# Sensor-TSL2591.net
KiCad netlist of a schematic drawn in EAGLE
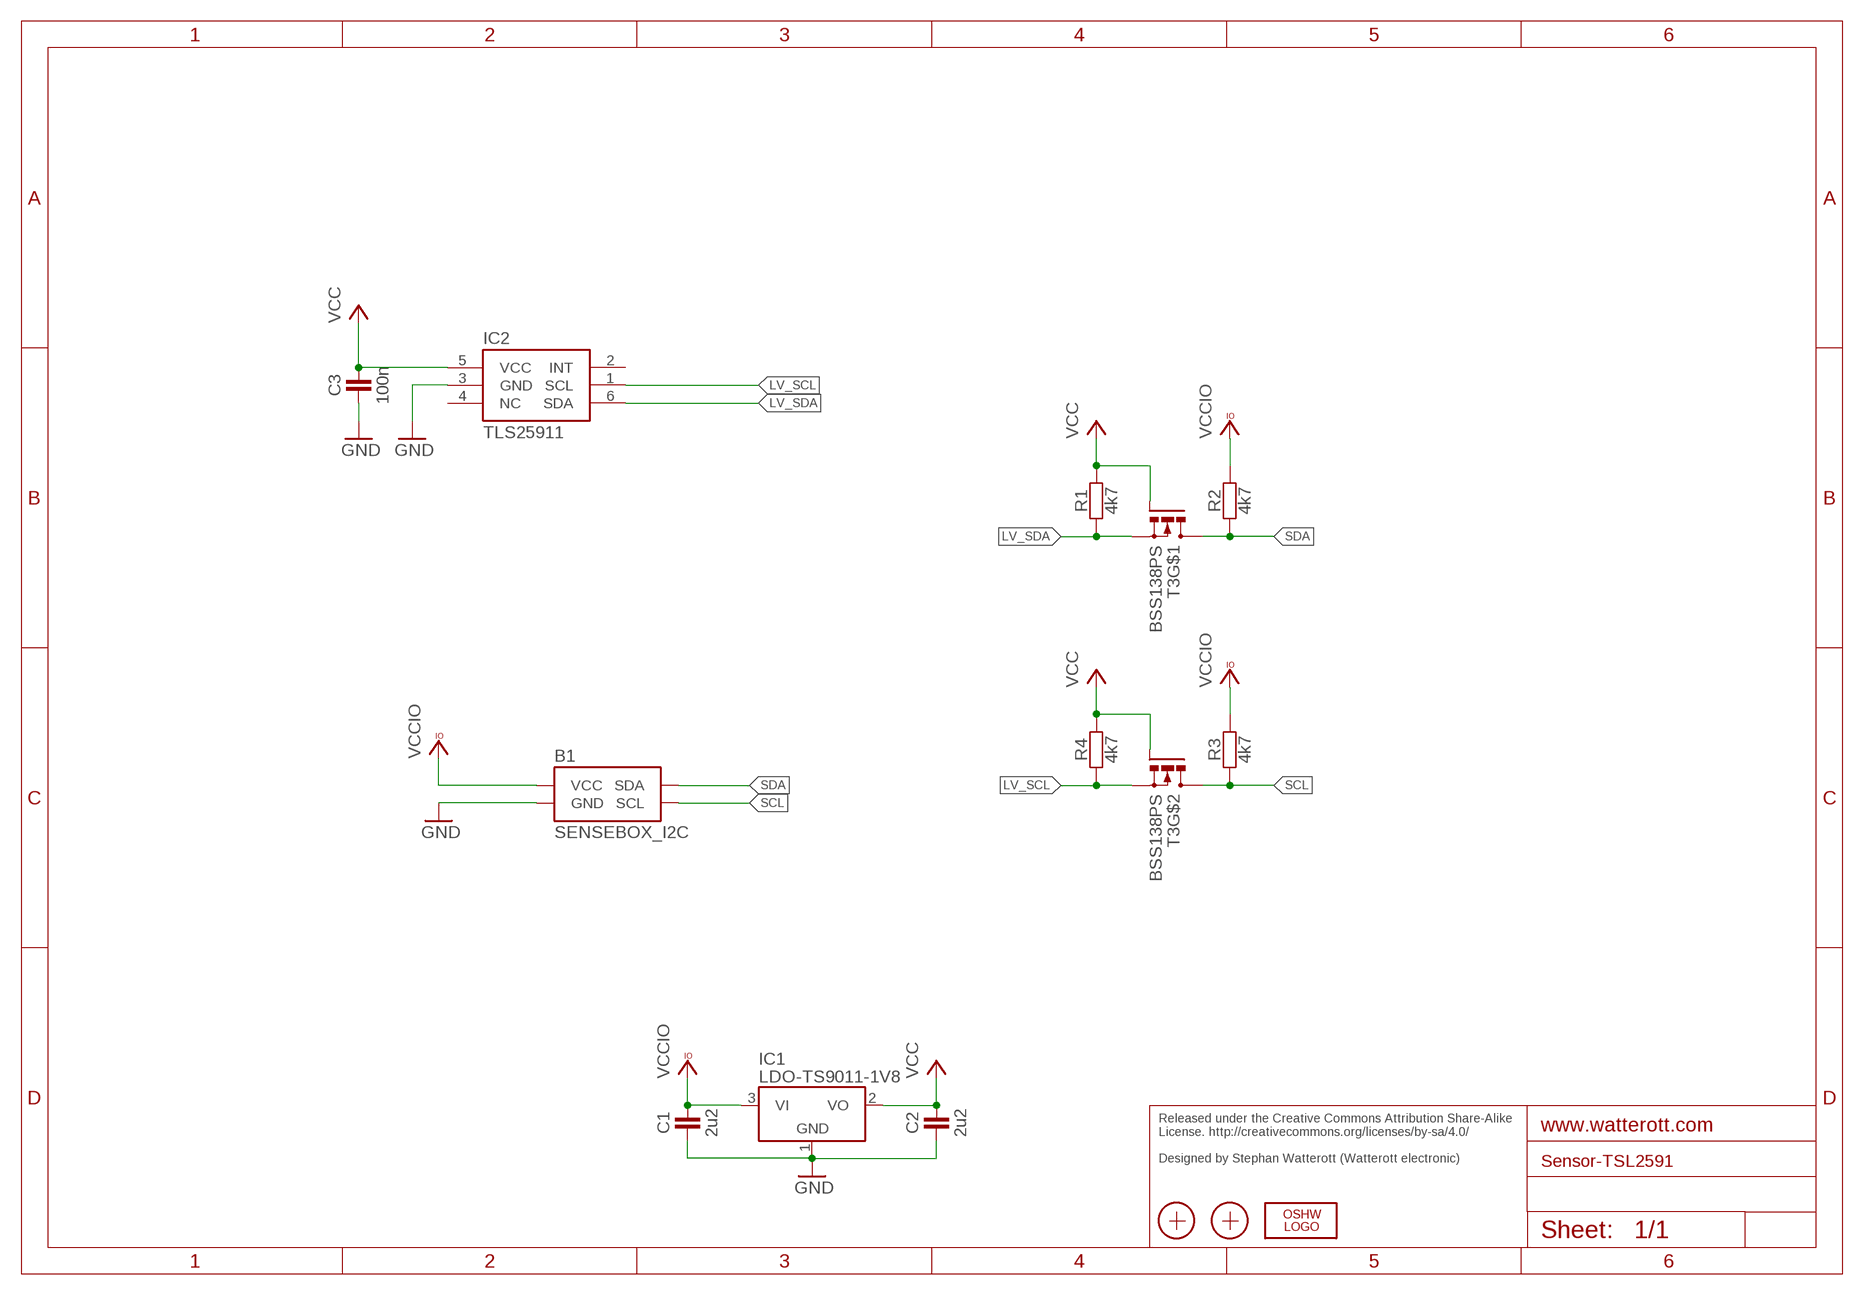
[diagram p0: schematic, sheet 1]

(export (version "E")
  (design (tool "Eeschema 10.0.6"))
  (components
    (comp (ref "B1")
      (value "SENSEBOX_I2C")
      (footprint "eagle-import:BREAKOUT_SENSEBOX_I2C")
      (libsource (lib "eagle-import") (part "SENSEBOX_I2C"))
    )
    (comp (ref "C1")
      (value "2u2")
      (footprint "eagle-import:R0402")
      (libsource (lib "eagle-import") (part "CAPACITOR-C0402"))
    )
    (comp (ref "C2")
      (value "2u2")
      (footprint "eagle-import:R0402")
      (libsource (lib "eagle-import") (part "CAPACITOR-C0402"))
    )
    (comp (ref "C3")
      (value "100n")
      (footprint "eagle-import:R0402")
      (libsource (lib "eagle-import") (part "CAPACITOR-C0402"))
    )
    (comp (ref "IC1")
      (value "LDO-TS9011-1V8")
      (footprint "eagle-import:SOT23")
      (libsource (lib "eagle-import") (part "LDO-TS9011-3V3"))
    )
    (comp (ref "IC2")
      (value "TLS25911")
      (footprint "eagle-import:WFDFN6")
      (libsource (lib "eagle-import") (part "TLS2591"))
    )
    (comp (ref "LOGO2")
      (value "OSHW_LOGOX0070")
      (footprint "eagle-import:OSHW_6X70")
      (libsource (lib "eagle-import") (part "OSHW_LOGOX0070"))
    )
    (comp (ref "R1")
      (value "4k7")
      (footprint "eagle-import:R0402")
      (libsource (lib "eagle-import") (part "RESISTOR-R0402"))
    )
    (comp (ref "R2")
      (value "4k7")
      (footprint "eagle-import:R0402")
      (libsource (lib "eagle-import") (part "RESISTOR-R0402"))
    )
    (comp (ref "R3")
      (value "4k7")
      (footprint "eagle-import:R0402")
      (libsource (lib "eagle-import") (part "RESISTOR-R0402"))
    )
    (comp (ref "R4")
      (value "4k7")
      (footprint "eagle-import:R0402")
      (libsource (lib "eagle-import") (part "RESISTOR-R0402"))
    )
    (comp (ref "T3")
      (value "BSS138PS")
      (footprint "eagle-import:SOT363")
      (libsource (lib "eagle-import") (part "BSS138PS"))
    )
    (comp (ref "X1")
      (value "PASSER-07")
      (footprint "eagle-import:PASSER_07MM")
      (libsource (lib "eagle-import") (part "PASSER-07"))
    )
    (comp (ref "X2")
      (value "PASSER-07")
      (footprint "eagle-import:PASSER_07MM")
      (libsource (lib "eagle-import") (part "PASSER-07"))
    )
  )
  (nets
    (net (code "1") (name "GND") (class "Default")
      (node (ref "B1") (pin "GND") (pinfunction "GND_GND") (pintype "power_in"))
      (node (ref "C1") (pin "1") (pinfunction "1_1") (pintype "passive"))
      (node (ref "C2") (pin "1") (pinfunction "1_1") (pintype "passive"))
      (node (ref "C3") (pin "1") (pinfunction "1_1") (pintype "passive"))
      (node (ref "IC1") (pin "1") (pinfunction "GND_1") (pintype "passive"))
      (node (ref "IC2") (pin "3") (pinfunction "GND_3") (pintype "power_in"))
    )
    (net (code "2") (name "LV_SCL") (class "Default")
      (node (ref "IC2") (pin "1") (pinfunction "SCL_1") (pintype "input"))
      (node (ref "R4") (pin "1") (pinfunction "1_1") (pintype "passive"))
      (node (ref "T3") (pin "4") (pinfunction "S_4") (pintype "passive"))
    )
    (net (code "3") (name "LV_SDA") (class "Default")
      (node (ref "IC2") (pin "6") (pinfunction "SDA_6") (pintype "output"))
      (node (ref "R1") (pin "1") (pinfunction "1_1") (pintype "passive"))
      (node (ref "T3") (pin "1") (pinfunction "S_1") (pintype "passive"))
    )
    (net (code "4") (name "SCL") (class "Default")
      (node (ref "B1") (pin "SCL") (pinfunction "SCL_SCL") (pintype "bidirectional"))
      (node (ref "R3") (pin "1") (pinfunction "1_1") (pintype "passive"))
      (node (ref "T3") (pin "3") (pinfunction "D_3") (pintype "passive"))
    )
    (net (code "5") (name "SDA") (class "Default")
      (node (ref "B1") (pin "SDA") (pinfunction "SDA_SDA") (pintype "bidirectional"))
      (node (ref "R2") (pin "1") (pinfunction "1_1") (pintype "passive"))
      (node (ref "T3") (pin "6") (pinfunction "D_6") (pintype "passive"))
    )
    (net (code "6") (name "VCC") (class "Default")
      (node (ref "C2") (pin "2") (pinfunction "2_2") (pintype "passive"))
      (node (ref "C3") (pin "2") (pinfunction "2_2") (pintype "passive"))
      (node (ref "IC1") (pin "2") (pinfunction "VO_2") (pintype "passive"))
      (node (ref "IC2") (pin "5") (pinfunction "VCC_5") (pintype "power_in"))
      (node (ref "R1") (pin "2") (pinfunction "2_2") (pintype "passive"))
      (node (ref "R4") (pin "2") (pinfunction "2_2") (pintype "passive"))
      (node (ref "T3") (pin "2") (pinfunction "G_2") (pintype "passive"))
      (node (ref "T3") (pin "5") (pinfunction "G_5") (pintype "passive"))
    )
    (net (code "7") (name "VCCIO") (class "Default")
      (node (ref "B1") (pin "VCC") (pinfunction "VCC_VCC") (pintype "power_in"))
      (node (ref "C1") (pin "2") (pinfunction "2_2") (pintype "passive"))
      (node (ref "IC1") (pin "3") (pinfunction "VI_3") (pintype "input"))
      (node (ref "R2") (pin "2") (pinfunction "2_2") (pintype "passive"))
      (node (ref "R3") (pin "2") (pinfunction "2_2") (pintype "passive"))
    )
    (net (code "8") (name "unconnected-(IC2-INT-Pad2)") (class "Default")
      (node (ref "IC2") (pin "2") (pinfunction "INT_2") (pintype "open_collector"))
    )
    (net (code "9") (name "unconnected-(IC2-NC-Pad4)") (class "Default")
      (node (ref "IC2") (pin "4") (pinfunction "NC_4") (pintype "no_connect"))
    )
  )
)
